# untitled_v2.net
KiCad netlist of a schematic drawn in EAGLE
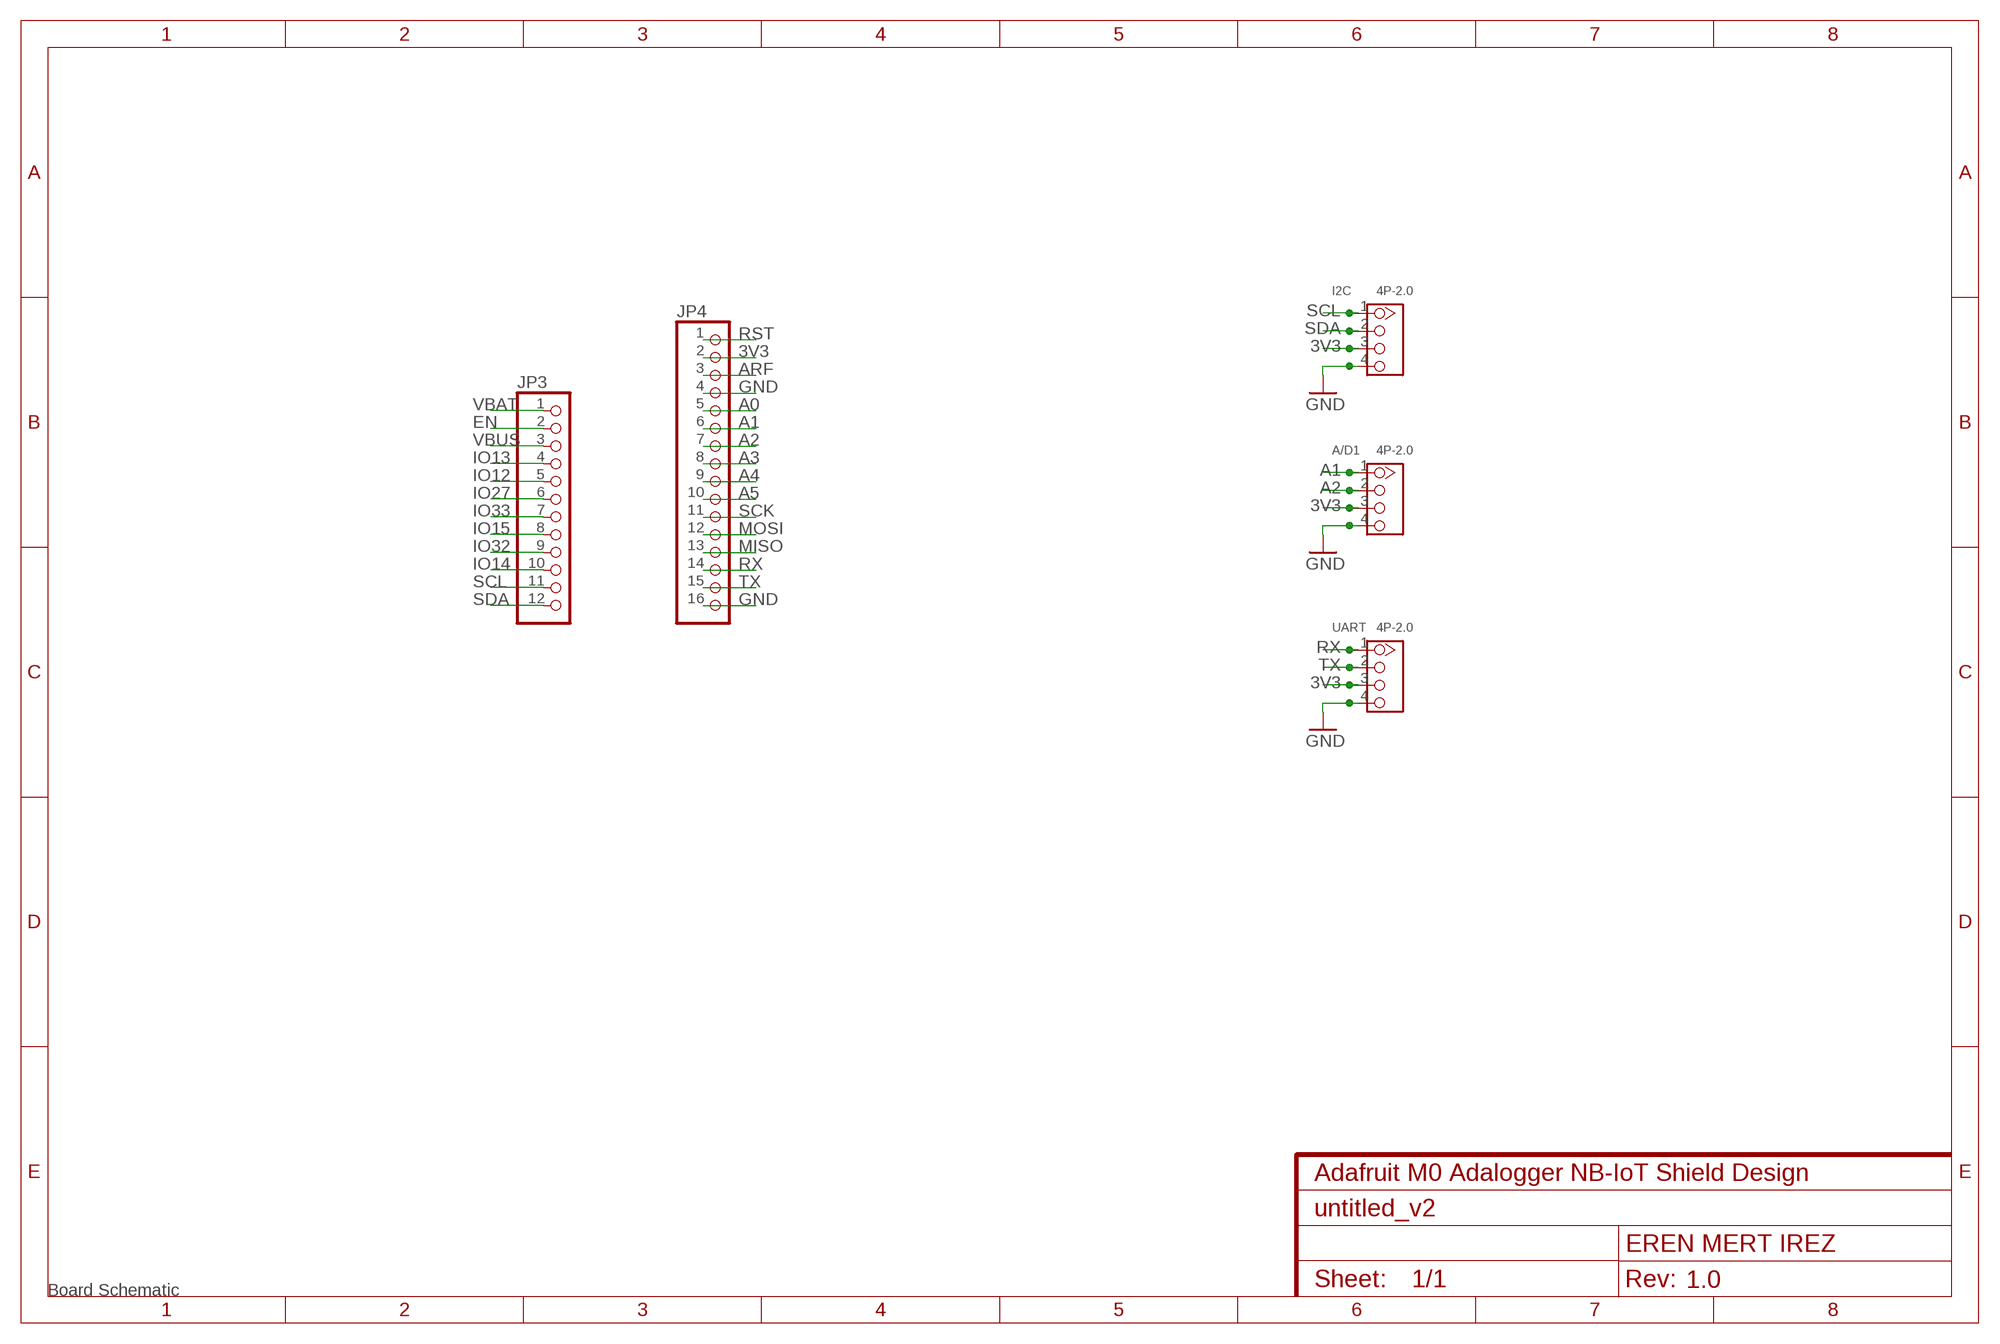
[diagram p0: schematic, sheet 1]

(export (version "E")
  (design (tool "Eeschema 10.0.6"))
  (components
    (comp (ref "A/D1")
      (value "4P-2.0")
      (footprint "eagle-import:HW4-2.0")
      (libsource (lib "eagle-import") (part "GROVE-CONNECTOR-DIP(4P-2.0)"))
    )
    (comp (ref "I2C")
      (value "4P-2.0")
      (footprint "eagle-import:HW4-2.0")
      (libsource (lib "eagle-import") (part "GROVE-CONNECTOR-DIP(4P-2.0)"))
    )
    (comp (ref "JP3")
      (value "PINHD-1X12")
      (footprint "eagle-import:1X12")
      (libsource (lib "eagle-import") (part "PINHD-1X12"))
    )
    (comp (ref "JP4")
      (value "PINHD-1X16")
      (footprint "eagle-import:1X16")
      (libsource (lib "eagle-import") (part "PINHD-1X16"))
    )
    (comp (ref "UART")
      (value "4P-2.0")
      (footprint "eagle-import:HW4-2.0")
      (libsource (lib "eagle-import") (part "GROVE-CONNECTOR-DIP(4P-2.0)"))
    )
  )
  (nets
    (net (code "1") (name "/3V3") (class "Default")
      (node (ref "A/D1") (pin "3") (pinfunction "3_3") (pintype "bidirectional"))
      (node (ref "I2C") (pin "3") (pinfunction "3_3") (pintype "bidirectional"))
      (node (ref "JP4") (pin "2") (pinfunction "2_2") (pintype "passive"))
      (node (ref "UART") (pin "3") (pinfunction "3_3") (pintype "bidirectional"))
    )
    (net (code "2") (name "/A0") (class "Default")
      (node (ref "JP4") (pin "5") (pinfunction "5_5") (pintype "passive"))
    )
    (net (code "3") (name "/A1") (class "Default")
      (node (ref "A/D1") (pin "1") (pinfunction "1_1") (pintype "bidirectional"))
      (node (ref "JP4") (pin "6") (pinfunction "6_6") (pintype "passive"))
    )
    (net (code "4") (name "/A2") (class "Default")
      (node (ref "A/D1") (pin "2") (pinfunction "2_2") (pintype "bidirectional"))
      (node (ref "JP4") (pin "7") (pinfunction "7_7") (pintype "passive"))
    )
    (net (code "5") (name "/A3") (class "Default")
      (node (ref "JP4") (pin "8") (pinfunction "8_8") (pintype "passive"))
    )
    (net (code "6") (name "/A4") (class "Default")
      (node (ref "JP4") (pin "9") (pinfunction "9_9") (pintype "passive"))
    )
    (net (code "7") (name "/A5") (class "Default")
      (node (ref "JP4") (pin "10") (pinfunction "10_10") (pintype "passive"))
    )
    (net (code "8") (name "/ARF") (class "Default")
      (node (ref "JP4") (pin "3") (pinfunction "3_3") (pintype "passive"))
    )
    (net (code "9") (name "/EN") (class "Default")
      (node (ref "JP3") (pin "2") (pinfunction "2_2") (pintype "passive"))
    )
    (net (code "10") (name "/IO12") (class "Default")
      (node (ref "JP3") (pin "5") (pinfunction "5_5") (pintype "passive"))
    )
    (net (code "11") (name "/IO13") (class "Default")
      (node (ref "JP3") (pin "4") (pinfunction "4_4") (pintype "passive"))
    )
    (net (code "12") (name "/IO14") (class "Default")
      (node (ref "JP3") (pin "10") (pinfunction "10_10") (pintype "passive"))
    )
    (net (code "13") (name "/IO15") (class "Default")
      (node (ref "JP3") (pin "8") (pinfunction "8_8") (pintype "passive"))
    )
    (net (code "14") (name "/IO27") (class "Default")
      (node (ref "JP3") (pin "6") (pinfunction "6_6") (pintype "passive"))
    )
    (net (code "15") (name "/IO32") (class "Default")
      (node (ref "JP3") (pin "9") (pinfunction "9_9") (pintype "passive"))
    )
    (net (code "16") (name "/IO33") (class "Default")
      (node (ref "JP3") (pin "7") (pinfunction "7_7") (pintype "passive"))
    )
    (net (code "17") (name "/MISO") (class "Default")
      (node (ref "JP4") (pin "13") (pinfunction "13_13") (pintype "passive"))
    )
    (net (code "18") (name "/MOSI") (class "Default")
      (node (ref "JP4") (pin "12") (pinfunction "12_12") (pintype "passive"))
    )
    (net (code "19") (name "/RST") (class "Default")
      (node (ref "JP4") (pin "1") (pinfunction "1_1") (pintype "passive"))
    )
    (net (code "20") (name "/RX") (class "Default")
      (node (ref "JP4") (pin "14") (pinfunction "14_14") (pintype "passive"))
      (node (ref "UART") (pin "1") (pinfunction "1_1") (pintype "bidirectional"))
    )
    (net (code "21") (name "/SCK") (class "Default")
      (node (ref "JP4") (pin "11") (pinfunction "11_11") (pintype "passive"))
    )
    (net (code "22") (name "/SCL") (class "Default")
      (node (ref "I2C") (pin "1") (pinfunction "1_1") (pintype "bidirectional"))
      (node (ref "JP3") (pin "11") (pinfunction "11_11") (pintype "passive"))
    )
    (net (code "23") (name "/SDA") (class "Default")
      (node (ref "I2C") (pin "2") (pinfunction "2_2") (pintype "bidirectional"))
      (node (ref "JP3") (pin "12") (pinfunction "12_12") (pintype "passive"))
    )
    (net (code "24") (name "/TX") (class "Default")
      (node (ref "JP4") (pin "15") (pinfunction "15_15") (pintype "passive"))
      (node (ref "UART") (pin "2") (pinfunction "2_2") (pintype "bidirectional"))
    )
    (net (code "25") (name "/VBAT") (class "Default")
      (node (ref "JP3") (pin "1") (pinfunction "1_1") (pintype "passive"))
    )
    (net (code "26") (name "/VBUS") (class "Default")
      (node (ref "JP3") (pin "3") (pinfunction "3_3") (pintype "passive"))
    )
    (net (code "27") (name "GND") (class "Default")
      (node (ref "A/D1") (pin "4") (pinfunction "4_4") (pintype "bidirectional"))
      (node (ref "I2C") (pin "4") (pinfunction "4_4") (pintype "bidirectional"))
      (node (ref "JP4") (pin "16") (pinfunction "16_16") (pintype "passive"))
      (node (ref "JP4") (pin "4") (pinfunction "4_4") (pintype "passive"))
      (node (ref "UART") (pin "4") (pinfunction "4_4") (pintype "bidirectional"))
    )
  )
)
